# Main.net
KiCad netlist of a schematic drawn in EAGLE
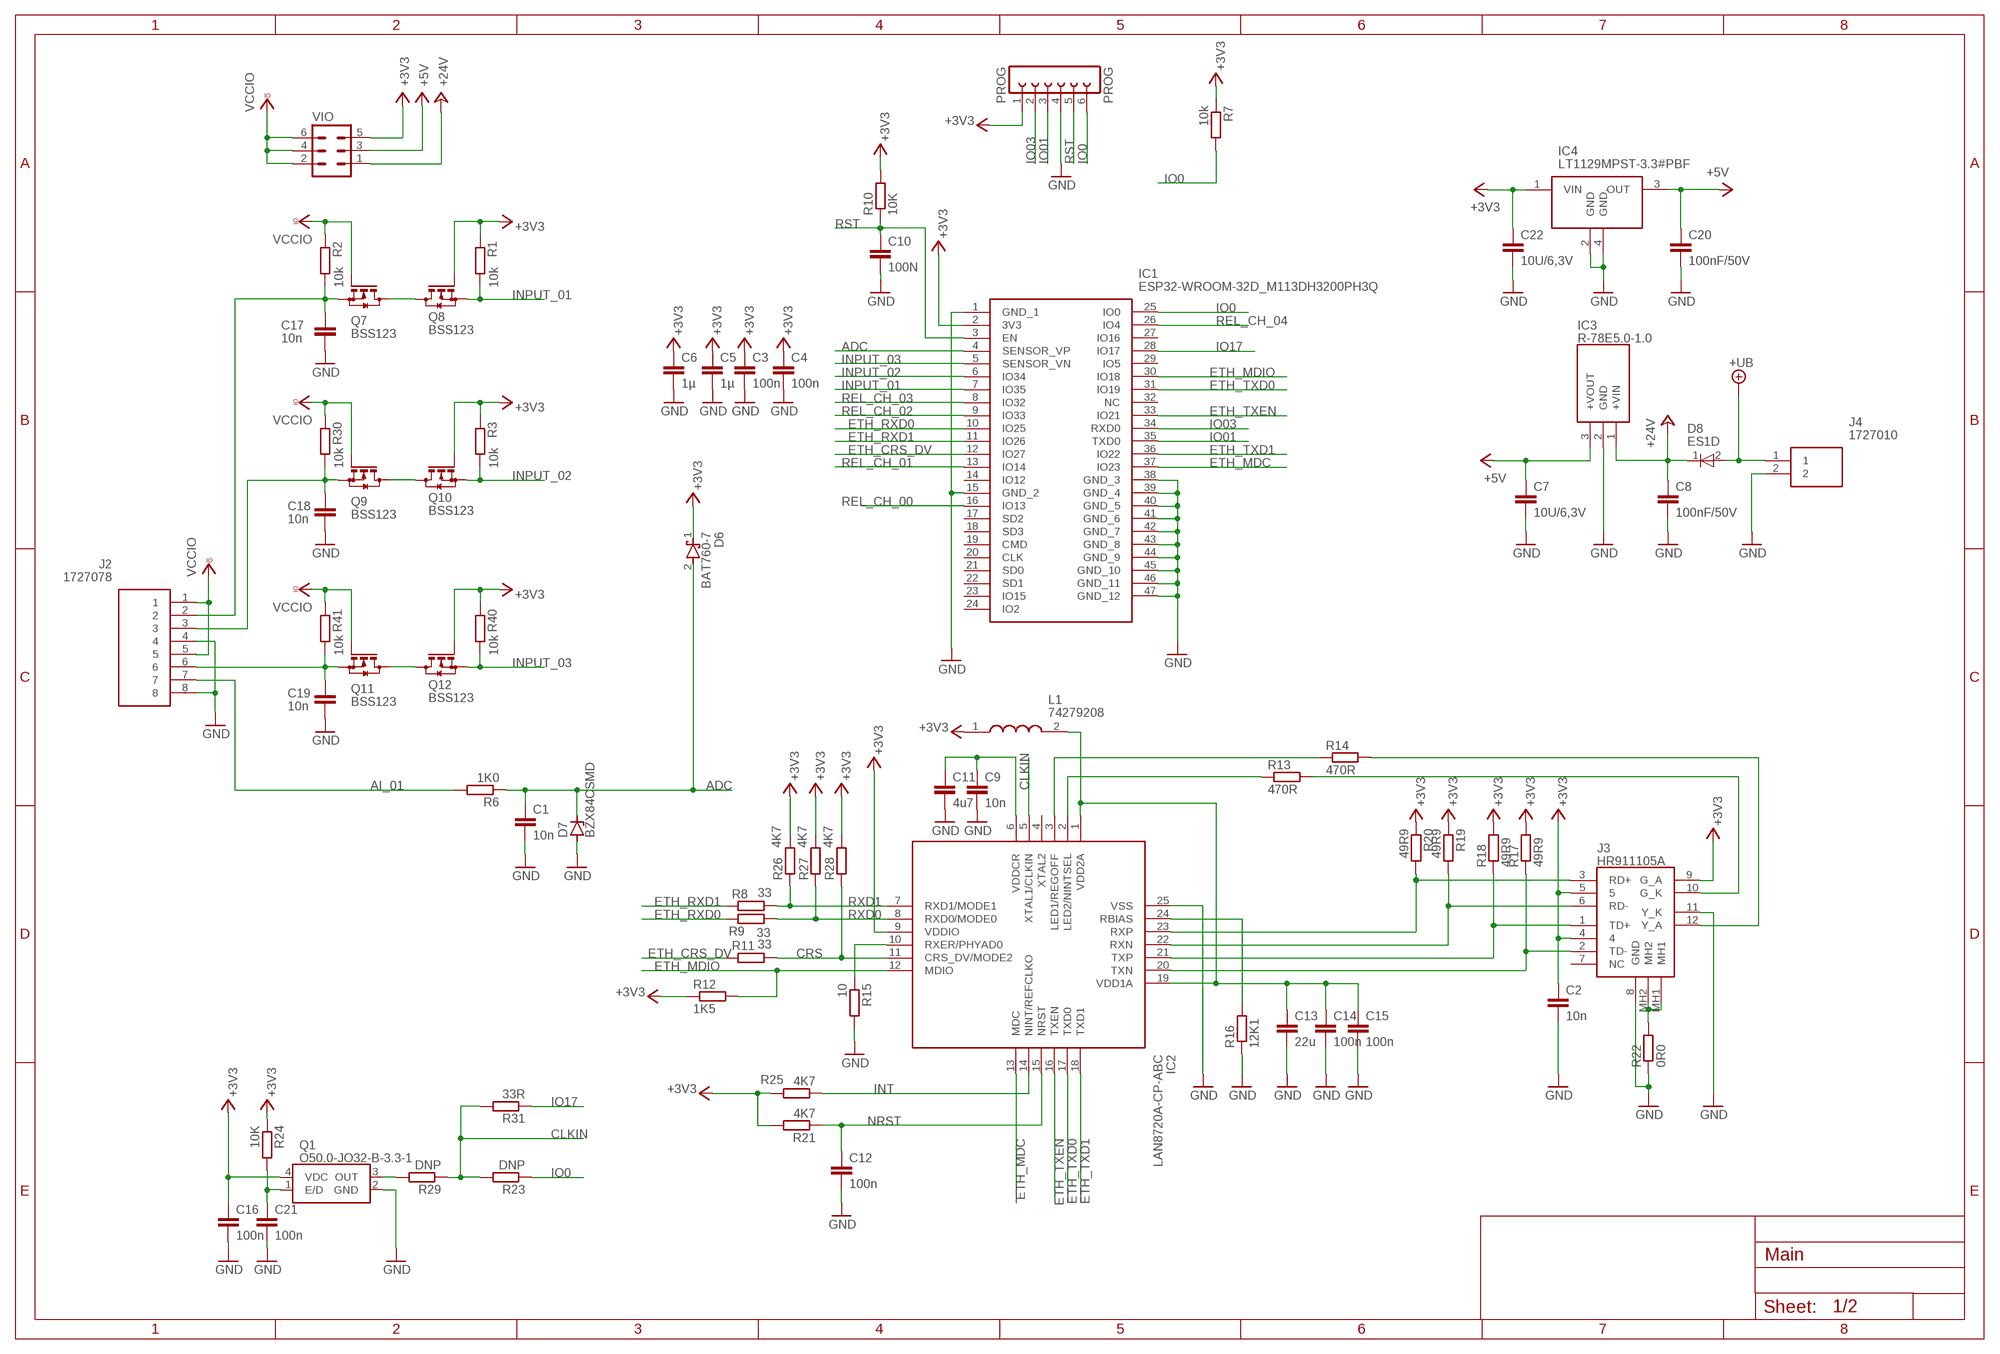
[diagram p0: schematic, sheet 1]
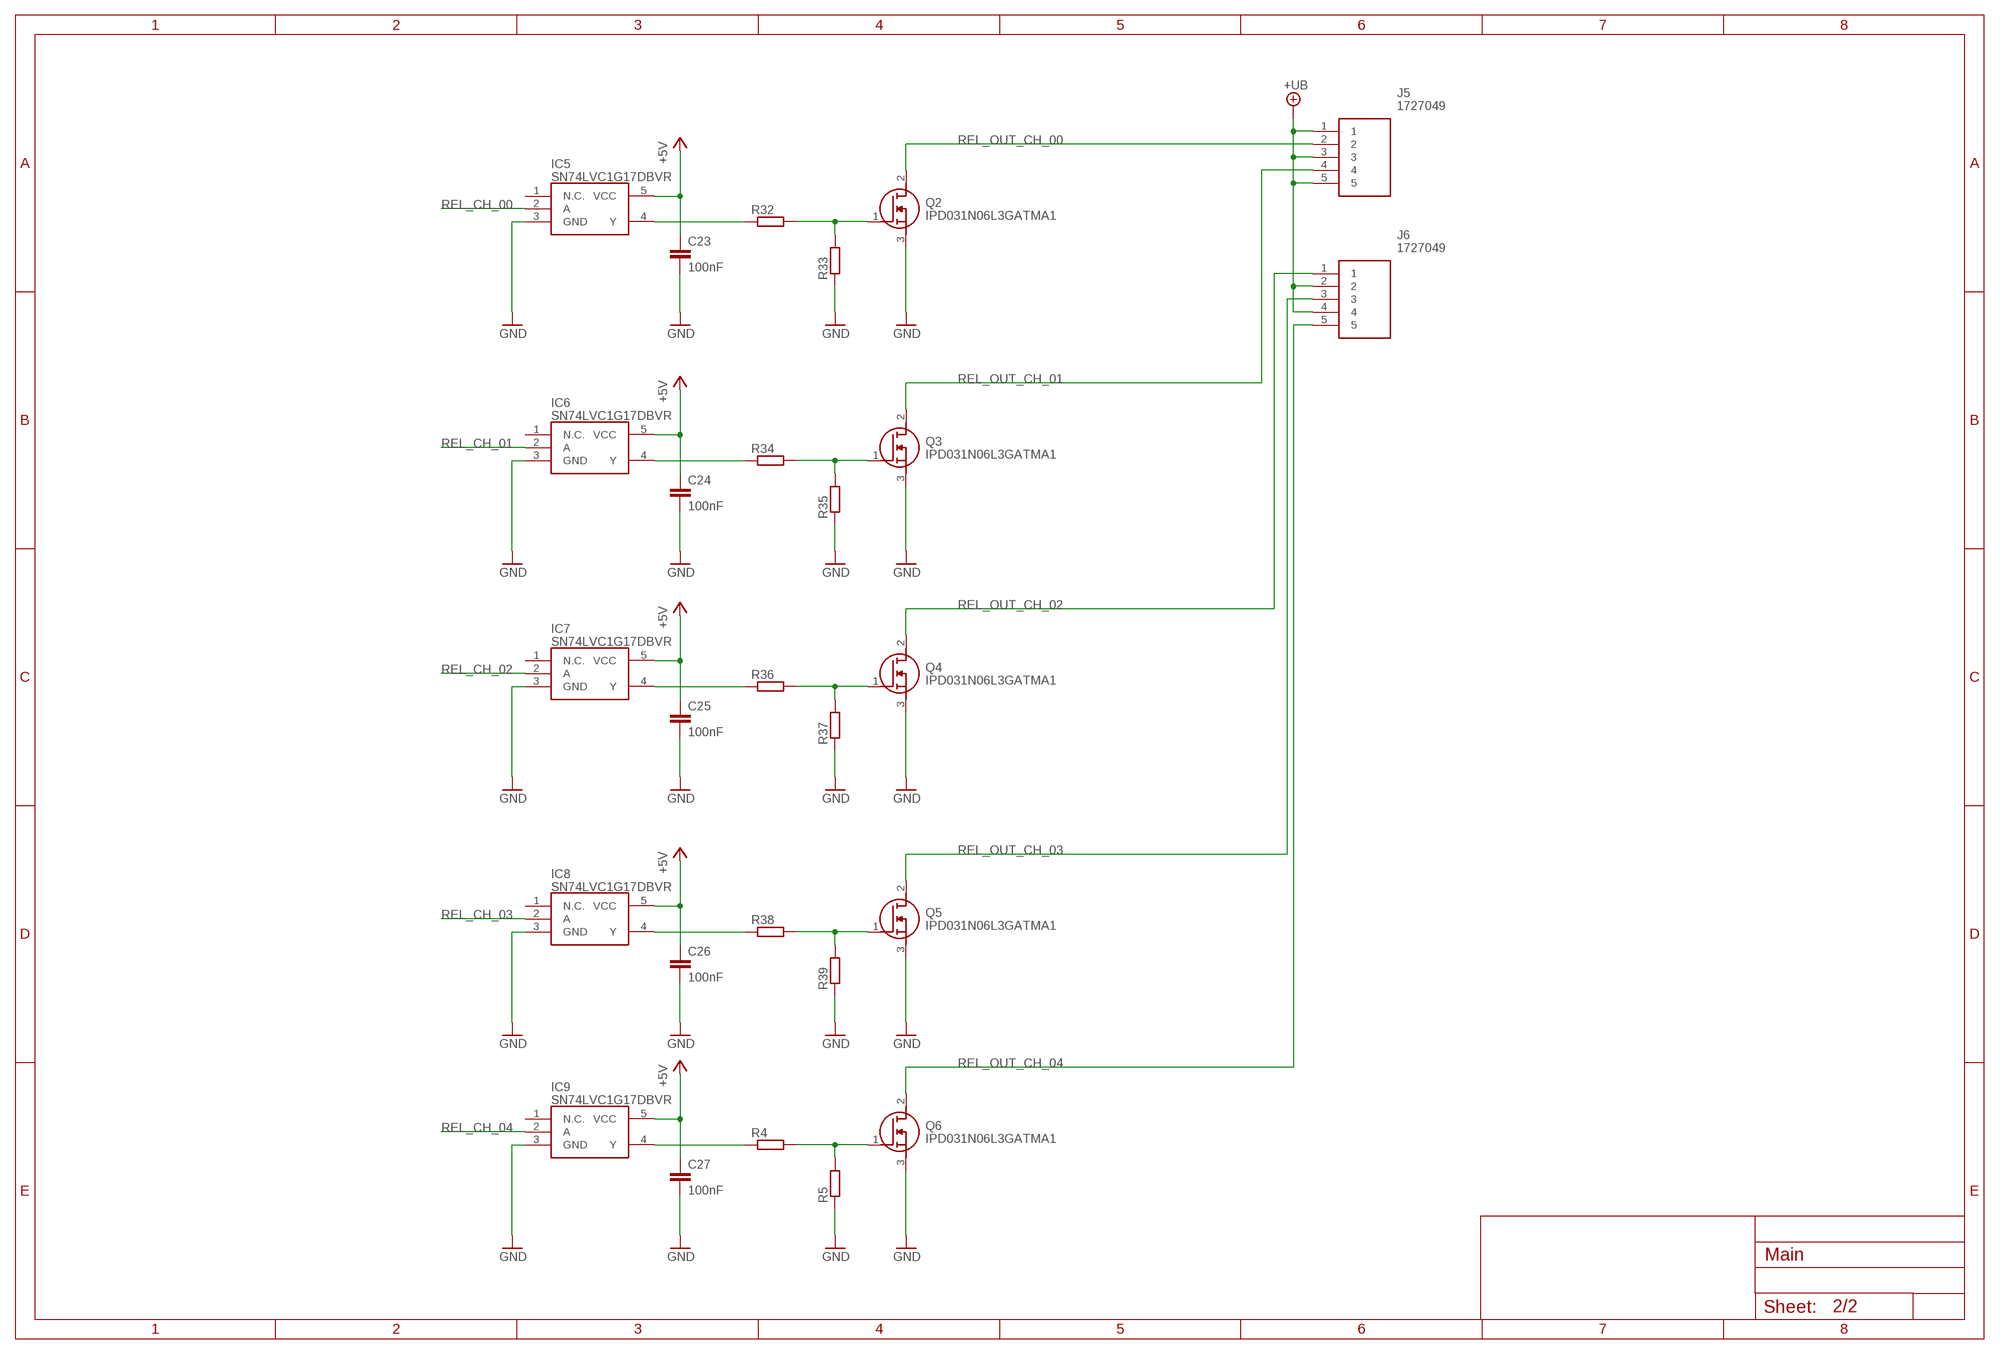
[diagram p1: schematic, sheet 2]

(export (version "E")
  (design (tool "Eeschema 10.0.6"))
  (components
    (comp (ref "C23")
      (value "100nF")
      (footprint "eagle-import:C0603")
      (libsource (lib "eagle-import") (part "C-EUC0603"))
    )
    (comp (ref "C24")
      (value "100nF")
      (footprint "eagle-import:C0603")
      (libsource (lib "eagle-import") (part "C-EUC0603"))
    )
    (comp (ref "C25")
      (value "100nF")
      (footprint "eagle-import:C0603")
      (libsource (lib "eagle-import") (part "C-EUC0603"))
    )
    (comp (ref "C26")
      (value "100nF")
      (footprint "eagle-import:C0603")
      (libsource (lib "eagle-import") (part "C-EUC0603"))
    )
    (comp (ref "C27")
      (value "100nF")
      (footprint "eagle-import:C0603")
      (libsource (lib "eagle-import") (part "C-EUC0603"))
    )
    (comp (ref "IC5")
      (value "SN74LVC1G17DBVR")
      (footprint "eagle-import:SOT95P280X145-5N")
      (fields (field (name "MOUSER_PART_NUMBER") "595-SN74LVC1G17DBVR"))
      (libsource (lib "eagle-import") (part "SN74LVC1G17DBVR"))
    )
    (comp (ref "IC6")
      (value "SN74LVC1G17DBVR")
      (footprint "eagle-import:SOT95P280X145-5N")
      (fields (field (name "MOUSER_PART_NUMBER") "595-SN74LVC1G17DBVR"))
      (libsource (lib "eagle-import") (part "SN74LVC1G17DBVR"))
    )
    (comp (ref "IC7")
      (value "SN74LVC1G17DBVR")
      (footprint "eagle-import:SOT95P280X145-5N")
      (fields (field (name "MOUSER_PART_NUMBER") "595-SN74LVC1G17DBVR"))
      (libsource (lib "eagle-import") (part "SN74LVC1G17DBVR"))
    )
    (comp (ref "IC8")
      (value "SN74LVC1G17DBVR")
      (footprint "eagle-import:SOT95P280X145-5N")
      (fields (field (name "MOUSER_PART_NUMBER") "595-SN74LVC1G17DBVR"))
      (libsource (lib "eagle-import") (part "SN74LVC1G17DBVR"))
    )
    (comp (ref "IC9")
      (value "SN74LVC1G17DBVR")
      (footprint "eagle-import:SOT95P280X145-5N")
      (fields (field (name "MOUSER_PART_NUMBER") "595-SN74LVC1G17DBVR"))
      (libsource (lib "eagle-import") (part "SN74LVC1G17DBVR"))
    )
    (comp (ref "J5")
      (value "1727049")
      (footprint "eagle-import:1727049")
      (fields (field (name "MOUSER_PART_NUMBER") "651-1727049"))
      (libsource (lib "eagle-import") (part "1727049"))
    )
    (comp (ref "J6")
      (value "1727049")
      (footprint "eagle-import:1727049")
      (fields (field (name "MOUSER_PART_NUMBER") "651-1727049"))
      (libsource (lib "eagle-import") (part "1727049"))
    )
    (comp (ref "Q2")
      (value "IPD031N06L3GATMA1")
      (footprint "eagle-import:IPD031N06L3GATMA1")
      (fields (field (name "MOUSER_PART_NUMBER") "726-IPD031N06L3GATMA"))
      (libsource (lib "eagle-import") (part "IPD031N06L3GATMA1"))
    )
    (comp (ref "Q3")
      (value "IPD031N06L3GATMA1")
      (footprint "eagle-import:IPD031N06L3GATMA1")
      (fields (field (name "MOUSER_PART_NUMBER") "726-IPD031N06L3GATMA"))
      (libsource (lib "eagle-import") (part "IPD031N06L3GATMA1"))
    )
    (comp (ref "Q4")
      (value "IPD031N06L3GATMA1")
      (footprint "eagle-import:IPD031N06L3GATMA1")
      (fields (field (name "MOUSER_PART_NUMBER") "726-IPD031N06L3GATMA"))
      (libsource (lib "eagle-import") (part "IPD031N06L3GATMA1"))
    )
    (comp (ref "Q5")
      (value "IPD031N06L3GATMA1")
      (footprint "eagle-import:IPD031N06L3GATMA1")
      (fields (field (name "MOUSER_PART_NUMBER") "726-IPD031N06L3GATMA"))
      (libsource (lib "eagle-import") (part "IPD031N06L3GATMA1"))
    )
    (comp (ref "Q6")
      (value "IPD031N06L3GATMA1")
      (footprint "eagle-import:IPD031N06L3GATMA1")
      (fields (field (name "MOUSER_PART_NUMBER") "726-IPD031N06L3GATMA"))
      (libsource (lib "eagle-import") (part "IPD031N06L3GATMA1"))
    )
    (comp (ref "R4")
      (value "R-EU_R0603")
      (footprint "eagle-import:R0603")
      (libsource (lib "eagle-import") (part "R-EU_R0603"))
    )
    (comp (ref "R5")
      (value "R-EU_R0603")
      (footprint "eagle-import:R0603")
      (libsource (lib "eagle-import") (part "R-EU_R0603"))
    )
    (comp (ref "R32")
      (value "R-EU_R0603")
      (footprint "eagle-import:R0603")
      (libsource (lib "eagle-import") (part "R-EU_R0603"))
    )
    (comp (ref "R33")
      (value "R-EU_R0603")
      (footprint "eagle-import:R0603")
      (libsource (lib "eagle-import") (part "R-EU_R0603"))
    )
    (comp (ref "R34")
      (value "R-EU_R0603")
      (footprint "eagle-import:R0603")
      (libsource (lib "eagle-import") (part "R-EU_R0603"))
    )
    (comp (ref "R35")
      (value "R-EU_R0603")
      (footprint "eagle-import:R0603")
      (libsource (lib "eagle-import") (part "R-EU_R0603"))
    )
    (comp (ref "R36")
      (value "R-EU_R0603")
      (footprint "eagle-import:R0603")
      (libsource (lib "eagle-import") (part "R-EU_R0603"))
    )
    (comp (ref "R37")
      (value "R-EU_R0603")
      (footprint "eagle-import:R0603")
      (libsource (lib "eagle-import") (part "R-EU_R0603"))
    )
    (comp (ref "R38")
      (value "R-EU_R0603")
      (footprint "eagle-import:R0603")
      (libsource (lib "eagle-import") (part "R-EU_R0603"))
    )
    (comp (ref "R39")
      (value "R-EU_R0603")
      (footprint "eagle-import:R0603")
      (libsource (lib "eagle-import") (part "R-EU_R0603"))
    )
    (comp (ref "C1")
      (value "10n")
      (footprint "eagle-import:C0603")
      (libsource (lib "eagle-import") (part "C-EUC0603"))
    )
    (comp (ref "C2")
      (value "10n")
      (footprint "eagle-import:C0603")
      (libsource (lib "eagle-import") (part "C-EUC0603"))
    )
    (comp (ref "C3")
      (value "100n")
      (footprint "eagle-import:C0603")
      (libsource (lib "eagle-import") (part "C-EUC0603"))
    )
    (comp (ref "C4")
      (value "100n")
      (footprint "eagle-import:C0603")
      (libsource (lib "eagle-import") (part "C-EUC0603"))
    )
    (comp (ref "C5")
      (value "1µ")
      (footprint "eagle-import:C0603")
      (libsource (lib "eagle-import") (part "C-EUC0603"))
    )
    (comp (ref "C6")
      (value "1µ")
      (footprint "eagle-import:C0603")
      (libsource (lib "eagle-import") (part "C-EUC0603"))
    )
    (comp (ref "C7")
      (value "10U/6,3V")
      (footprint "eagle-import:C0603")
      (libsource (lib "eagle-import") (part "C-EUC0603"))
    )
    (comp (ref "C8")
      (value "100nF/50V")
      (footprint "eagle-import:C0603")
      (libsource (lib "eagle-import") (part "C-EUC0603"))
    )
    (comp (ref "C9")
      (value "10n")
      (footprint "eagle-import:C0603")
      (libsource (lib "eagle-import") (part "C-EUC0603"))
    )
    (comp (ref "C10")
      (value "100N")
      (footprint "eagle-import:C0603")
      (libsource (lib "eagle-import") (part "C-EUC0603"))
    )
    (comp (ref "C11")
      (value "4u7")
      (footprint "eagle-import:C0603")
      (libsource (lib "eagle-import") (part "C-EUC0603"))
    )
    (comp (ref "C12")
      (value "100n")
      (footprint "eagle-import:C0603")
      (libsource (lib "eagle-import") (part "C-EUC0603"))
    )
    (comp (ref "C13")
      (value "22u")
      (footprint "eagle-import:C0603")
      (libsource (lib "eagle-import") (part "C-EUC0603"))
    )
    (comp (ref "C14")
      (value "100n")
      (footprint "eagle-import:C0603")
      (libsource (lib "eagle-import") (part "C-EUC0603"))
    )
    (comp (ref "C15")
      (value "100n")
      (footprint "eagle-import:C0603")
      (libsource (lib "eagle-import") (part "C-EUC0603"))
    )
    (comp (ref "C16")
      (value "100n")
      (footprint "eagle-import:C0603")
      (libsource (lib "eagle-import") (part "C-EUC0603"))
    )
    (comp (ref "C17")
      (value "10n")
      (footprint "eagle-import:C0603")
      (libsource (lib "eagle-import") (part "C-EUC0603"))
    )
    (comp (ref "C18")
      (value "10n")
      (footprint "eagle-import:C0603")
      (libsource (lib "eagle-import") (part "C-EUC0603"))
    )
    (comp (ref "C19")
      (value "10n")
      (footprint "eagle-import:C0603")
      (libsource (lib "eagle-import") (part "C-EUC0603"))
    )
    (comp (ref "C20")
      (value "100nF/50V")
      (footprint "eagle-import:C0603")
      (libsource (lib "eagle-import") (part "C-EUC0603"))
    )
    (comp (ref "C21")
      (value "100n")
      (footprint "eagle-import:C0603")
      (libsource (lib "eagle-import") (part "C-EUC0603"))
    )
    (comp (ref "C22")
      (value "10U/6,3V")
      (footprint "eagle-import:C0603")
      (libsource (lib "eagle-import") (part "C-EUC0603"))
    )
    (comp (ref "D6")
      (value "BAT760-7")
      (footprint "eagle-import:SOD2513X120N")
      (fields (field (name "MOUSER_PART_NUMBER") "621-BAT760-7"))
      (libsource (lib "eagle-import") (part "BAT760-7"))
    )
    (comp (ref "D7")
      (value "BZX84CSMD")
      (footprint "eagle-import:TO236")
      (libsource (lib "eagle-import") (part "BZX84CSMD"))
    )
    (comp (ref "D8")
      (value "ES1D")
      (footprint "eagle-import:SODFL3618X143N")
      (fields
        (field (name "ARROW_PART_NUMBER") "ES1DL R3G")
        (field (name "MOUSER_PART_NUMBER") "821-ES1DLR3G")
      )
      (libsource (lib "eagle-import") (part "ES1DL_R3G"))
    )
    (comp (ref "IC1")
      (value "ESP32-WROOM-32D_M113DH3200PH3Q")
      (footprint "eagle-import:ESP32WROOM32DM113DH3200PH3Q0")
      (fields
        (field (name "MANUFACTURER_PART_NUMBER") "ESP32-WROOM-32D(M113DH3200PH3Q0)")
        (field (name "MOUSER_PART_NUMBER") "356-ESP32WROOM-32D")
      )
      (libsource (lib "eagle-import") (part "ESP32-WROOM-32D_M113DH3200PH3Q"))
    )
    (comp (ref "IC2")
      (value "LAN8720A-CP-ABC")
      (footprint "eagle-import:QFN50P400X400X100-25N")
      (fields (field (name "MOUSER_PART_NUMBER") "579-LAN8720ACPABC"))
      (libsource (lib "eagle-import") (part "LAN8720A-CP-ABC"))
    )
    (comp (ref "IC3")
      (value "R-78E5.0-1.0")
      (footprint "eagle-import:R78E3310")
      (fields
        (field (name "ARROW_PART_NUMBER") "R-78E3.3-1.0")
        (field (name "MOUSER_PART_NUMBER") "919-R-78E3.3-1.0")
      )
      (libsource (lib "eagle-import") (part "R-78E3.3-1.0"))
    )
    (comp (ref "IC4")
      (value "LT1129MPST-3.3#PBF")
      (footprint "eagle-import:SOT230P700X180-4N")
      (fields (field (name "MOUSER_PART_NUMBER") "584-1129MPST-3.3PBF"))
      (libsource (lib "eagle-import") (part "LT1129MPST-3.3#PBF"))
    )
    (comp (ref "J2")
      (value "1727078")
      (footprint "eagle-import:1727078")
      (fields (field (name "MOUSER_PART_NUMBER") "651-1727078"))
      (libsource (lib "eagle-import") (part "1727078"))
    )
    (comp (ref "J3")
      (value "HR911105A")
      (footprint "eagle-import:HR911105A")
      (libsource (lib "eagle-import") (part "HR911105A"))
    )
    (comp (ref "J4")
      (value "1727010")
      (footprint "eagle-import:1727010")
      (fields (field (name "MOUSER_PART_NUMBER") "651-1727010"))
      (libsource (lib "eagle-import") (part "1727010"))
    )
    (comp (ref "L1")
      (value "74279208")
      (footprint "eagle-import:CAPC2012X90N")
      (fields (field (name "MOUSER_PART_NUMBER") "710-74279208"))
      (libsource (lib "eagle-import") (part "74279208"))
    )
    (comp (ref "PROG")
      (value "PROG")
      (footprint "eagle-import:FE06")
      (libsource (lib "eagle-import") (part "FE06-1"))
    )
    (comp (ref "Q1")
      (value "O50.0-JO32-B-3.3-1")
      (footprint "eagle-import:O200JO32B1V31T1LF")
      (libsource (lib "eagle-import") (part "O50.0-JO32-B-3.3-1"))
    )
    (comp (ref "Q7")
      (value "BSS123")
      (footprint "eagle-import:SOT23")
      (libsource (lib "eagle-import") (part "BSS123"))
    )
    (comp (ref "Q8")
      (value "BSS123")
      (footprint "eagle-import:SOT23")
      (libsource (lib "eagle-import") (part "BSS123"))
    )
    (comp (ref "Q9")
      (value "BSS123")
      (footprint "eagle-import:SOT23")
      (libsource (lib "eagle-import") (part "BSS123"))
    )
    (comp (ref "Q10")
      (value "BSS123")
      (footprint "eagle-import:SOT23")
      (libsource (lib "eagle-import") (part "BSS123"))
    )
    (comp (ref "Q11")
      (value "BSS123")
      (footprint "eagle-import:SOT23")
      (libsource (lib "eagle-import") (part "BSS123"))
    )
    (comp (ref "Q12")
      (value "BSS123")
      (footprint "eagle-import:SOT23")
      (libsource (lib "eagle-import") (part "BSS123"))
    )
    (comp (ref "R1")
      (value "10k")
      (footprint "eagle-import:R0603")
      (libsource (lib "eagle-import") (part "R-EU_R0603"))
    )
    (comp (ref "R2")
      (value "10k")
      (footprint "eagle-import:R0603")
      (libsource (lib "eagle-import") (part "R-EU_R0603"))
    )
    (comp (ref "R3")
      (value "10k")
      (footprint "eagle-import:R0603")
      (libsource (lib "eagle-import") (part "R-EU_R0603"))
    )
    (comp (ref "R6")
      (value "1K0")
      (footprint "eagle-import:R0603")
      (libsource (lib "eagle-import") (part "R-EU_R0603"))
    )
    (comp (ref "R7")
      (value "10k")
      (footprint "eagle-import:R0603")
      (libsource (lib "eagle-import") (part "R-EU_R0603"))
    )
    (comp (ref "R8")
      (value "33")
      (footprint "eagle-import:R0603")
      (libsource (lib "eagle-import") (part "R-EU_R0603"))
    )
    (comp (ref "R9")
      (value "33")
      (footprint "eagle-import:R0603")
      (libsource (lib "eagle-import") (part "R-EU_R0603"))
    )
    (comp (ref "R10")
      (value "10K")
      (footprint "eagle-import:R0603")
      (libsource (lib "eagle-import") (part "R-EU_R0603"))
    )
    (comp (ref "R11")
      (value "33")
      (footprint "eagle-import:R0603")
      (libsource (lib "eagle-import") (part "R-EU_R0603"))
    )
    (comp (ref "R12")
      (value "1K5")
      (footprint "eagle-import:R0603")
      (libsource (lib "eagle-import") (part "R-EU_R0603"))
    )
    (comp (ref "R13")
      (value "470R")
      (footprint "eagle-import:R0603")
      (libsource (lib "eagle-import") (part "R-EU_R0603"))
    )
    (comp (ref "R14")
      (value "470R")
      (footprint "eagle-import:R0603")
      (libsource (lib "eagle-import") (part "R-EU_R0603"))
    )
    (comp (ref "R15")
      (value "10")
      (footprint "eagle-import:R0603")
      (libsource (lib "eagle-import") (part "R-EU_R0603"))
    )
    (comp (ref "R16")
      (value "12K1")
      (footprint "eagle-import:R0603")
      (libsource (lib "eagle-import") (part "R-EU_R0603"))
    )
    (comp (ref "R17")
      (value "49R9")
      (footprint "eagle-import:R0603")
      (libsource (lib "eagle-import") (part "R-EU_R0603"))
    )
    (comp (ref "R18")
      (value "49R9")
      (footprint "eagle-import:R0603")
      (libsource (lib "eagle-import") (part "R-EU_R0603"))
    )
    (comp (ref "R19")
      (value "49R9")
      (footprint "eagle-import:R0603")
      (libsource (lib "eagle-import") (part "R-EU_R0603"))
    )
    (comp (ref "R20")
      (value "49R9")
      (footprint "eagle-import:R0603")
      (libsource (lib "eagle-import") (part "R-EU_R0603"))
    )
    (comp (ref "R21")
      (value "4K7")
      (footprint "eagle-import:R0603")
      (libsource (lib "eagle-import") (part "R-EU_R0603"))
    )
    (comp (ref "R22")
      (value "0R0")
      (footprint "eagle-import:R0603")
      (libsource (lib "eagle-import") (part "R-EU_R0603"))
    )
    (comp (ref "R23")
      (value "DNP")
      (footprint "eagle-import:R0603")
      (libsource (lib "eagle-import") (part "R-EU_R0603"))
    )
    (comp (ref "R24")
      (value "10K")
      (footprint "eagle-import:R0603")
      (libsource (lib "eagle-import") (part "R-EU_R0603"))
    )
    (comp (ref "R25")
      (value "4K7")
      (footprint "eagle-import:R0603")
      (libsource (lib "eagle-import") (part "R-EU_R0603"))
    )
    (comp (ref "R26")
      (value "4K7")
      (footprint "eagle-import:R0603")
      (libsource (lib "eagle-import") (part "R-EU_R0603"))
    )
    (comp (ref "R27")
      (value "4K7")
      (footprint "eagle-import:R0603")
      (libsource (lib "eagle-import") (part "R-EU_R0603"))
    )
    (comp (ref "R28")
      (value "4K7")
      (footprint "eagle-import:R0603")
      (libsource (lib "eagle-import") (part "R-EU_R0603"))
    )
    (comp (ref "R29")
      (value "DNP")
      (footprint "eagle-import:R0603")
      (libsource (lib "eagle-import") (part "R-EU_R0603"))
    )
    (comp (ref "R30")
      (value "10k")
      (footprint "eagle-import:R0603")
      (libsource (lib "eagle-import") (part "R-EU_R0603"))
    )
    (comp (ref "R31")
      (value "33R")
      (footprint "eagle-import:R0603")
      (libsource (lib "eagle-import") (part "R-EU_R0603"))
    )
    (comp (ref "R40")
      (value "10k")
      (footprint "eagle-import:R0603")
      (libsource (lib "eagle-import") (part "R-EU_R0603"))
    )
    (comp (ref "R41")
      (value "10k")
      (footprint "eagle-import:R0603")
      (libsource (lib "eagle-import") (part "R-EU_R0603"))
    )
    (comp (ref "VIO")
      (value "MA03-2")
      (footprint "eagle-import:MA03-2")
      (libsource (lib "eagle-import") (part "MA03-2"))
    )
  )
  (nets
    (net (code "1") (name "+3V3") (class "Default")
      (node (ref "C16") (pin "1") (pinfunction "1_1") (pintype "passive"))
      (node (ref "C2") (pin "1") (pinfunction "1_1") (pintype "passive"))
      (node (ref "C22") (pin "1") (pinfunction "1_1") (pintype "passive"))
      (node (ref "C3") (pin "1") (pinfunction "1_1") (pintype "passive"))
      (node (ref "C4") (pin "1") (pinfunction "1_1") (pintype "passive"))
      (node (ref "C5") (pin "1") (pinfunction "1_1") (pintype "passive"))
      (node (ref "C6") (pin "1") (pinfunction "1_1") (pintype "passive"))
      (node (ref "D6") (pin "1") (pinfunction "K_1") (pintype "passive"))
      (node (ref "IC1") (pin "2") (pinfunction "3V3_2") (pintype "bidirectional"))
      (node (ref "IC2") (pin "9") (pinfunction "VDDIO_9") (pintype "bidirectional"))
      (node (ref "IC4") (pin "1") (pinfunction "VIN_1") (pintype "bidirectional"))
      (node (ref "J3") (pin "4") (pinfunction "4_4") (pintype "bidirectional"))
      (node (ref "J3") (pin "5") (pinfunction "5_5") (pintype "bidirectional"))
      (node (ref "J3") (pin "9") (pinfunction "G_A_9") (pintype "bidirectional"))
      (node (ref "L1") (pin "1") (pinfunction "1_1") (pintype "bidirectional"))
      (node (ref "PROG") (pin "1") (pinfunction "1_1") (pintype "passive"))
      (node (ref "Q1") (pin "4") (pinfunction "VDC_4") (pintype "bidirectional"))
      (node (ref "Q10") (pin "1") (pinfunction "G_1") (pintype "passive"))
      (node (ref "Q12") (pin "1") (pinfunction "G_1") (pintype "passive"))
      (node (ref "Q8") (pin "1") (pinfunction "G_1") (pintype "passive"))
      (node (ref "R1") (pin "1") (pinfunction "1_1") (pintype "passive"))
      (node (ref "R10") (pin "2") (pinfunction "2_2") (pintype "passive"))
      (node (ref "R12") (pin "1") (pinfunction "1_1") (pintype "passive"))
      (node (ref "R17") (pin "2") (pinfunction "2_2") (pintype "passive"))
      (node (ref "R18") (pin "2") (pinfunction "2_2") (pintype "passive"))
      (node (ref "R19") (pin "1") (pinfunction "1_1") (pintype "passive"))
      (node (ref "R20") (pin "1") (pinfunction "1_1") (pintype "passive"))
      (node (ref "R21") (pin "2") (pinfunction "2_2") (pintype "passive"))
      (node (ref "R24") (pin "1") (pinfunction "1_1") (pintype "passive"))
      (node (ref "R25") (pin "2") (pinfunction "2_2") (pintype "passive"))
      (node (ref "R26") (pin "2") (pinfunction "2_2") (pintype "passive"))
      (node (ref "R27") (pin "2") (pinfunction "2_2") (pintype "passive"))
      (node (ref "R28") (pin "2") (pinfunction "2_2") (pintype "passive"))
      (node (ref "R3") (pin "1") (pinfunction "1_1") (pintype "passive"))
      (node (ref "R40") (pin "1") (pinfunction "1_1") (pintype "passive"))
      (node (ref "R7") (pin "1") (pinfunction "1_1") (pintype "passive"))
      (node (ref "VIO") (pin "5") (pinfunction "5_5") (pintype "passive"))
    )
    (net (code "2") (name "+5V") (class "Default")
      (node (ref "C20") (pin "1") (pinfunction "1_1") (pintype "passive"))
      (node (ref "C23") (pin "1") (pinfunction "1_1") (pintype "passive"))
      (node (ref "C24") (pin "1") (pinfunction "1_1") (pintype "passive"))
      (node (ref "C25") (pin "1") (pinfunction "1_1") (pintype "passive"))
      (node (ref "C26") (pin "1") (pinfunction "1_1") (pintype "passive"))
      (node (ref "C27") (pin "1") (pinfunction "1_1") (pintype "passive"))
      (node (ref "C7") (pin "1") (pinfunction "1_1") (pintype "passive"))
      (node (ref "IC3") (pin "3") (pinfunction "+VOUT_3") (pintype "bidirectional"))
      (node (ref "IC4") (pin "3") (pinfunction "OUT_3") (pintype "bidirectional"))
      (node (ref "IC5") (pin "5") (pinfunction "VCC_5") (pintype "bidirectional"))
      (node (ref "IC6") (pin "5") (pinfunction "VCC_5") (pintype "bidirectional"))
      (node (ref "IC7") (pin "5") (pinfunction "VCC_5") (pintype "bidirectional"))
      (node (ref "IC8") (pin "5") (pinfunction "VCC_5") (pintype "bidirectional"))
      (node (ref "IC9") (pin "5") (pinfunction "VCC_5") (pintype "bidirectional"))
      (node (ref "VIO") (pin "3") (pinfunction "3_3") (pintype "passive"))
    )
    (net (code "3") (name "+24V") (class "Default")
      (node (ref "C8") (pin "1") (pinfunction "1_1") (pintype "passive"))
      (node (ref "D8") (pin "1") (pinfunction "K_1") (pintype "bidirectional"))
      (node (ref "IC3") (pin "1") (pinfunction "+VIN_1") (pintype "bidirectional"))
      (node (ref "VIO") (pin "1") (pinfunction "1_1") (pintype "passive"))
    )
    (net (code "4") (name "+UB") (class "Default")
      (node (ref "D8") (pin "2") (pinfunction "A_2") (pintype "bidirectional"))
      (node (ref "J4") (pin "1") (pinfunction "1_1") (pintype "bidirectional"))
      (node (ref "J5") (pin "1") (pinfunction "1_1") (pintype "bidirectional"))
      (node (ref "J5") (pin "3") (pinfunction "3_3") (pintype "bidirectional"))
      (node (ref "J5") (pin "5") (pinfunction "5_5") (pintype "bidirectional"))
      (node (ref "J6") (pin "2") (pinfunction "2_2") (pintype "bidirectional"))
      (node (ref "J6") (pin "4") (pinfunction "4_4") (pintype "bidirectional"))
    )
    (net (code "5") (name "ADC") (class "Default")
      (node (ref "C1") (pin "1") (pinfunction "1_1") (pintype "passive"))
      (node (ref "D6") (pin "2") (pinfunction "A_2") (pintype "passive"))
      (node (ref "D7") (pin "C") (pinfunction "C_C") (pintype "passive"))
      (node (ref "IC1") (pin "4") (pinfunction "SENSOR_VP_4") (pintype "bidirectional"))
      (node (ref "R6") (pin "1") (pinfunction "1_1") (pintype "passive"))
    )
    (net (code "6") (name "AI_01") (class "Default")
      (node (ref "J2") (pin "7") (pinfunction "7_7") (pintype "bidirectional"))
      (node (ref "R6") (pin "2") (pinfunction "2_2") (pintype "passive"))
    )
    (net (code "7") (name "CLKIN") (class "Default")
      (node (ref "IC2") (pin "5") (pinfunction "XTAL1/CLKIN_5") (pintype "bidirectional"))
      (node (ref "R23") (pin "2") (pinfunction "2_2") (pintype "passive"))
      (node (ref "R29") (pin "1") (pinfunction "1_1") (pintype "passive"))
      (node (ref "R31") (pin "2") (pinfunction "2_2") (pintype "passive"))
    )
    (net (code "8") (name "CRS") (class "Default")
      (node (ref "IC2") (pin "11") (pinfunction "CRS_DV/MODE2_11") (pintype "bidirectional"))
      (node (ref "R11") (pin "2") (pinfunction "2_2") (pintype "passive"))
      (node (ref "R28") (pin "1") (pinfunction "1_1") (pintype "passive"))
    )
    (net (code "9") (name "ETH_CRS_DV") (class "Default")
      (node (ref "IC1") (pin "12") (pinfunction "IO27_12") (pintype "bidirectional"))
      (node (ref "R11") (pin "1") (pinfunction "1_1") (pintype "passive"))
    )
    (net (code "10") (name "ETH_MDC") (class "Default")
      (node (ref "IC1") (pin "37") (pinfunction "IO23_37") (pintype "bidirectional"))
      (node (ref "IC2") (pin "13") (pinfunction "MDC_13") (pintype "bidirectional"))
    )
    (net (code "11") (name "ETH_MDIO") (class "Default")
      (node (ref "IC1") (pin "30") (pinfunction "IO18_30") (pintype "bidirectional"))
      (node (ref "IC2") (pin "12") (pinfunction "MDIO_12") (pintype "bidirectional"))
      (node (ref "R12") (pin "2") (pinfunction "2_2") (pintype "passive"))
    )
    (net (code "12") (name "ETH_RXD0") (class "Default")
      (node (ref "IC1") (pin "10") (pinfunction "IO25_10") (pintype "bidirectional"))
      (node (ref "R9") (pin "1") (pinfunction "1_1") (pintype "passive"))
    )
    (net (code "13") (name "ETH_RXD1") (class "Default")
      (node (ref "IC1") (pin "11") (pinfunction "IO26_11") (pintype "bidirectional"))
      (node (ref "R8") (pin "1") (pinfunction "1_1") (pintype "passive"))
    )
    (net (code "14") (name "ETH_TXD0") (class "Default")
      (node (ref "IC1") (pin "31") (pinfunction "IO19_31") (pintype "bidirectional"))
      (node (ref "IC2") (pin "17") (pinfunction "TXD0_17") (pintype "bidirectional"))
    )
    (net (code "15") (name "ETH_TXD1") (class "Default")
      (node (ref "IC1") (pin "36") (pinfunction "IO22_36") (pintype "bidirectional"))
      (node (ref "IC2") (pin "18") (pinfunction "TXD1_18") (pintype "bidirectional"))
    )
    (net (code "16") (name "ETH_TXEN") (class "Default")
      (node (ref "IC1") (pin "33") (pinfunction "IO21_33") (pintype "bidirectional"))
      (node (ref "IC2") (pin "16") (pinfunction "TXEN_16") (pintype "bidirectional"))
    )
    (net (code "17") (name "GND") (class "Default")
      (node (ref "C1") (pin "2") (pinfunction "2_2") (pintype "passive"))
      (node (ref "C10") (pin "2") (pinfunction "2_2") (pintype "passive"))
      (node (ref "C11") (pin "2") (pinfunction "2_2") (pintype "passive"))
      (node (ref "C12") (pin "2") (pinfunction "2_2") (pintype "passive"))
      (node (ref "C13") (pin "2") (pinfunction "2_2") (pintype "passive"))
      (node (ref "C14") (pin "2") (pinfunction "2_2") (pintype "passive"))
      (node (ref "C15") (pin "2") (pinfunction "2_2") (pintype "passive"))
      (node (ref "C16") (pin "2") (pinfunction "2_2") (pintype "passive"))
      (node (ref "C17") (pin "2") (pinfunction "2_2") (pintype "passive"))
      (node (ref "C18") (pin "2") (pinfunction "2_2") (pintype "passive"))
      (node (ref "C19") (pin "2") (pinfunction "2_2") (pintype "passive"))
      (node (ref "C2") (pin "2") (pinfunction "2_2") (pintype "passive"))
      (node (ref "C20") (pin "2") (pinfunction "2_2") (pintype "passive"))
      (node (ref "C21") (pin "2") (pinfunction "2_2") (pintype "passive"))
      (node (ref "C22") (pin "2") (pinfunction "2_2") (pintype "passive"))
      (node (ref "C23") (pin "2") (pinfunction "2_2") (pintype "passive"))
      (node (ref "C24") (pin "2") (pinfunction "2_2") (pintype "passive"))
      (node (ref "C25") (pin "2") (pinfunction "2_2") (pintype "passive"))
      (node (ref "C26") (pin "2") (pinfunction "2_2") (pintype "passive"))
      (node (ref "C27") (pin "2") (pinfunction "2_2") (pintype "passive"))
      (node (ref "C3") (pin "2") (pinfunction "2_2") (pintype "passive"))
      (node (ref "C4") (pin "2") (pinfunction "2_2") (pintype "passive"))
      (node (ref "C5") (pin "2") (pinfunction "2_2") (pintype "passive"))
      (node (ref "C6") (pin "2") (pinfunction "2_2") (pintype "passive"))
      (node (ref "C7") (pin "2") (pinfunction "2_2") (pintype "passive"))
      (node (ref "C8") (pin "2") (pinfunction "2_2") (pintype "passive"))
      (node (ref "C9") (pin "2") (pinfunction "2_2") (pintype "passive"))
      (node (ref "D7") (pin "A") (pinfunction "A_A") (pintype "passive"))
      (node (ref "IC1") (pin "1") (pinfunction "GND_1_1") (pintype "bidirectional"))
      (node (ref "IC1") (pin "15") (pinfunction "GND_2_15") (pintype "bidirectional"))
      (node (ref "IC1") (pin "38") (pinfunction "GND_3_38") (pintype "bidirectional"))
      (node (ref "IC1") (pin "39") (pinfunction "GND_4_39") (pintype "bidirectional"))
      (node (ref "IC1") (pin "40") (pinfunction "GND_5_40") (pintype "bidirectional"))
      (node (ref "IC1") (pin "41") (pinfunction "GND_6_41") (pintype "bidirectional"))
      (node (ref "IC1") (pin "42") (pinfunction "GND_7_42") (pintype "bidirectional"))
      (node (ref "IC1") (pin "43") (pinfunction "GND_8_43") (pintype "bidirectional"))
      (node (ref "IC1") (pin "44") (pinfunction "GND_9_44") (pintype "bidirectional"))
      (node (ref "IC1") (pin "45") (pinfunction "GND_10_45") (pintype "bidirectional"))
      (node (ref "IC1") (pin "46") (pinfunction "GND_11_46") (pintype "bidirectional"))
      (node (ref "IC1") (pin "47") (pinfunction "GND_12_47") (pintype "bidirectional"))
      (node (ref "IC2") (pin "25") (pinfunction "VSS_25") (pintype "bidirectional"))
      (node (ref "IC3") (pin "2") (pinfunction "GND_2") (pintype "bidirectional"))
      (node (ref "IC4") (pin "2") (pinfunction "GND_2") (pintype "bidirectional"))
      (node (ref "IC4") (pin "4") (pinfunction "GND._4") (pintype "bidirectional"))
      (node (ref "IC5") (pin "3") (pinfunction "GND_3") (pintype "bidirectional"))
      (node (ref "IC6") (pin "3") (pinfunction "GND_3") (pintype "bidirectional"))
      (node (ref "IC7") (pin "3") (pinfunction "GND_3") (pintype "bidirectional"))
      (node (ref "IC8") (pin "3") (pinfunction "GND_3") (pintype "bidirectional"))
      (node (ref "IC9") (pin "3") (pinfunction "GND_3") (pintype "bidirectional"))
      (node (ref "J2") (pin "4") (pinfunction "4_4") (pintype "bidirectional"))
      (node (ref "J2") (pin "8") (pinfunction "8_8") (pintype "bidirectional"))
      (node (ref "J3") (pin "11") (pinfunction "Y_K_11") (pintype "bidirectional"))
      (node (ref "J3") (pin "8") (pinfunction "GND_8") (pintype "bidirectional"))
      (node (ref "J4") (pin "2") (pinfunction "2_2") (pintype "bidirectional"))
      (node (ref "PROG") (pin "4") (pinfunction "4_4") (pintype "passive"))
      (node (ref "Q1") (pin "2") (pinfunction "GND_2") (pintype "bidirectional"))
      (node (ref "Q2") (pin "3") (pinfunction "S_3") (pintype "bidirectional"))
      (node (ref "Q3") (pin "3") (pinfunction "S_3") (pintype "bidirectional"))
      (node (ref "Q4") (pin "3") (pinfunction "S_3") (pintype "bidirectional"))
      (node (ref "Q5") (pin "3") (pinfunction "S_3") (pintype "bidirectional"))
      (node (ref "Q6") (pin "3") (pinfunction "S_3") (pintype "bidirectional"))
      (node (ref "R15") (pin "2") (pinfunction "2_2") (pintype "passive"))
      (node (ref "R16") (pin "1") (pinfunction "1_1") (pintype "passive"))
      (node (ref "R22") (pin "1") (pinfunction "1_1") (pintype "passive"))
      (node (ref "R33") (pin "1") (pinfunction "1_1") (pintype "passive"))
      (node (ref "R35") (pin "1") (pinfunction "1_1") (pintype "passive"))
      (node (ref "R37") (pin "1") (pinfunction "1_1") (pintype "passive"))
      (node (ref "R39") (pin "1") (pinfunction "1_1") (pintype "passive"))
      (node (ref "R5") (pin "1") (pinfunction "1_1") (pintype "passive"))
    )
    (net (code "18") (name "INPUT_01") (class "Default")
      (node (ref "IC1") (pin "7") (pinfunction "IO35_7") (pintype "bidirectional"))
      (node (ref "Q8") (pin "2") (pinfunction "S_2") (pintype "passive"))
      (node (ref "R1") (pin "2") (pinfunction "2_2") (pintype "passive"))
    )
    (net (code "19") (name "INPUT_02") (class "Default")
      (node (ref "IC1") (pin "6") (pinfunction "IO34_6") (pintype "bidirectional"))
      (node (ref "Q10") (pin "2") (pinfunction "S_2") (pintype "passive"))
      (node (ref "R3") (pin "2") (pinfunction "2_2") (pintype "passive"))
    )
    (net (code "20") (name "INPUT_03") (class "Default")
      (node (ref "IC1") (pin "5") (pinfunction "SENSOR_VN_5") (pintype "bidirectional"))
      (node (ref "Q12") (pin "2") (pinfunction "S_2") (pintype "passive"))
      (node (ref "R40") (pin "2") (pinfunction "2_2") (pintype "passive"))
    )
    (net (code "21") (name "INT") (class "Default")
      (node (ref "IC2") (pin "14") (pinfunction "NINT/REFCLKO_14") (pintype "bidirectional"))
      (node (ref "R25") (pin "1") (pinfunction "1_1") (pintype "passive"))
    )
    (net (code "22") (name "IO0") (class "Default")
      (node (ref "IC1") (pin "25") (pinfunction "IO0_25") (pintype "bidirectional"))
      (node (ref "PROG") (pin "6") (pinfunction "6_6") (pintype "passive"))
      (node (ref "R23") (pin "1") (pinfunction "1_1") (pintype "passive"))
      (node (ref "R7") (pin "2") (pinfunction "2_2") (pintype "passive"))
    )
    (net (code "23") (name "IO01") (class "Default")
      (node (ref "IC1") (pin "35") (pinfunction "TXD0_35") (pintype "bidirectional"))
      (node (ref "PROG") (pin "3") (pinfunction "3_3") (pintype "passive"))
    )
    (net (code "24") (name "IO03") (class "Default")
      (node (ref "IC1") (pin "34") (pinfunction "RXD0_34") (pintype "bidirectional"))
      (node (ref "PROG") (pin "2") (pinfunction "2_2") (pintype "passive"))
    )
    (net (code "25") (name "IO17") (class "Default")
      (node (ref "IC1") (pin "28") (pinfunction "IO17_28") (pintype "bidirectional"))
      (node (ref "R31") (pin "1") (pinfunction "1_1") (pintype "passive"))
    )
    (net (code "26") (name "NRST") (class "Default")
      (node (ref "C12") (pin "1") (pinfunction "1_1") (pintype "passive"))
      (node (ref "IC2") (pin "15") (pinfunction "NRST_15") (pintype "bidirectional"))
      (node (ref "R21") (pin "1") (pinfunction "1_1") (pintype "passive"))
    )
    (net (code "27") (name "Net-(IC2-LED1{slash}REGOFF)") (class "Default")
      (node (ref "IC2") (pin "3") (pinfunction "LED1/REGOFF_3") (pintype "bidirectional"))
      (node (ref "R14") (pin "1") (pinfunction "1_1") (pintype "passive"))
    )
    (net (code "28") (name "Net-(IC2-LED2{slash}NINTSEL)") (class "Default")
      (node (ref "IC2") (pin "2") (pinfunction "LED2/NINTSEL_2") (pintype "bidirectional"))
      (node (ref "R13") (pin "1") (pinfunction "1_1") (pintype "passive"))
    )
    (net (code "29") (name "Net-(IC2-RBIAS)") (class "Default")
      (node (ref "IC2") (pin "24") (pinfunction "RBIAS_24") (pintype "bidirectional"))
      (node (ref "R16") (pin "2") (pinfunction "2_2") (pintype "passive"))
    )
    (net (code "30") (name "Net-(IC2-RXER{slash}PHYAD0)") (class "Default")
      (node (ref "IC2") (pin "10") (pinfunction "RXER/PHYAD0_10") (pintype "bidirectional"))
      (node (ref "R15") (pin "1") (pinfunction "1_1") (pintype "passive"))
    )
    (net (code "31") (name "Net-(IC2-RXN)") (class "Default")
      (node (ref "IC2") (pin "22") (pinfunction "RXN_22") (pintype "bidirectional"))
      (node (ref "J3") (pin "6") (pinfunction "RD-_6") (pintype "bidirectional"))
      (node (ref "R19") (pin "2") (pinfunction "2_2") (pintype "passive"))
    )
    (net (code "32") (name "Net-(IC2-RXP)") (class "Default")
      (node (ref "IC2") (pin "23") (pinfunction "RXP_23") (pintype "bidirectional"))
      (node (ref "J3") (pin "3") (pinfunction "RD+_3") (pintype "bidirectional"))
      (node (ref "R20") (pin "2") (pinfunction "2_2") (pintype "passive"))
    )
    (net (code "33") (name "Net-(IC2-TXN)") (class "Default")
      (node (ref "IC2") (pin "20") (pinfunction "TXN_20") (pintype "bidirectional"))
      (node (ref "J3") (pin "2") (pinfunction "TD-_2") (pintype "bidirectional"))
      (node (ref "R17") (pin "1") (pinfunction "1_1") (pintype "passive"))
    )
    (net (code "34") (name "Net-(IC2-TXP)") (class "Default")
      (node (ref "IC2") (pin "21") (pinfunction "TXP_21") (pintype "bidirectional"))
      (node (ref "J3") (pin "1") (pinfunction "TD+_1") (pintype "bidirectional"))
      (node (ref "R18") (pin "1") (pinfunction "1_1") (pintype "passive"))
    )
    (net (code "35") (name "Net-(IC2-VDD1A)") (class "Default")
      (node (ref "C13") (pin "1") (pinfunction "1_1") (pintype "passive"))
      (node (ref "C14") (pin "1") (pinfunction "1_1") (pintype "passive"))
      (node (ref "C15") (pin "1") (pinfunction "1_1") (pintype "passive"))
      (node (ref "IC2") (pin "1") (pinfunction "VDD2A_1") (pintype "bidirectional"))
      (node (ref "IC2") (pin "19") (pinfunction "VDD1A_19") (pintype "bidirectional"))
      (node (ref "L1") (pin "2") (pinfunction "2_2") (pintype "bidirectional"))
    )
    (net (code "36") (name "Net-(IC2-VDDCR)") (class "Default")
      (node (ref "C11") (pin "1") (pinfunction "1_1") (pintype "passive"))
      (node (ref "C9") (pin "1") (pinfunction "1_1") (pintype "passive"))
      (node (ref "IC2") (pin "6") (pinfunction "VDDCR_6") (pintype "bidirectional"))
    )
    (net (code "37") (name "Net-(IC5-Y)") (class "Default")
      (node (ref "IC5") (pin "4") (pinfunction "Y_4") (pintype "bidirectional"))
      (node (ref "R32") (pin "1") (pinfunction "1_1") (pintype "passive"))
    )
    (net (code "38") (name "Net-(IC6-Y)") (class "Default")
      (node (ref "IC6") (pin "4") (pinfunction "Y_4") (pintype "bidirectional"))
      (node (ref "R34") (pin "1") (pinfunction "1_1") (pintype "passive"))
    )
    (net (code "39") (name "Net-(IC7-Y)") (class "Default")
      (node (ref "IC7") (pin "4") (pinfunction "Y_4") (pintype "bidirectional"))
      (node (ref "R36") (pin "1") (pinfunction "1_1") (pintype "passive"))
    )
    (net (code "40") (name "Net-(IC8-Y)") (class "Default")
      (node (ref "IC8") (pin "4") (pinfunction "Y_4") (pintype "bidirectional"))
      (node (ref "R38") (pin "1") (pinfunction "1_1") (pintype "passive"))
    )
    (net (code "41") (name "Net-(IC9-Y)") (class "Default")
      (node (ref "IC9") (pin "4") (pinfunction "Y_4") (pintype "bidirectional"))
      (node (ref "R4") (pin "1") (pinfunction "1_1") (pintype "passive"))
    )
    (net (code "42") (name "Net-(J3-G_K)") (class "Default")
      (node (ref "J3") (pin "10") (pinfunction "G_K_10") (pintype "bidirectional"))
      (node (ref "R13") (pin "2") (pinfunction "2_2") (pintype "passive"))
    )
    (net (code "43") (name "Net-(J3-PadMH1)") (class "Default")
      (node (ref "J3") (pin "MH1") (pinfunction "MH1_MH1") (pintype "bidirectional"))
      (node (ref "J3") (pin "MH2") (pinfunction "MH2_MH2") (pintype "bidirectional"))
      (node (ref "R22") (pin "2") (pinfunction "2_2") (pintype "passive"))
    )
    (net (code "44") (name "Net-(J3-Y_A)") (class "Default")
      (node (ref "J3") (pin "12") (pinfunction "Y_A_12") (pintype "bidirectional"))
      (node (ref "R14") (pin "2") (pinfunction "2_2") (pintype "passive"))
    )
    (net (code "45") (name "Net-(Q1-E{slash}D)") (class "Default")
      (node (ref "C21") (pin "1") (pinfunction "1_1") (pintype "passive"))
      (node (ref "Q1") (pin "1") (pinfunction "E/D_1") (pintype "bidirectional"))
      (node (ref "R24") (pin "2") (pinfunction "2_2") (pintype "passive"))
    )
    (net (code "46") (name "Net-(Q1-OUT)") (class "Default")
      (node (ref "Q1") (pin "3") (pinfunction "OUT_3") (pintype "bidirectional"))
      (node (ref "R29") (pin "2") (pinfunction "2_2") (pintype "passive"))
    )
    (net (code "47") (name "Net-(Q2-G)") (class "Default")
      (node (ref "Q2") (pin "1") (pinfunction "G_1") (pintype "bidirectional"))
      (node (ref "R32") (pin "2") (pinfunction "2_2") (pintype "passive"))
      (node (ref "R33") (pin "2") (pinfunction "2_2") (pintype "passive"))
    )
    (net (code "48") (name "Net-(Q3-G)") (class "Default")
      (node (ref "Q3") (pin "1") (pinfunction "G_1") (pintype "bidirectional"))
      (node (ref "R34") (pin "2") (pinfunction "2_2") (pintype "passive"))
      (node (ref "R35") (pin "2") (pinfunction "2_2") (pintype "passive"))
    )
    (net (code "49") (name "Net-(Q4-G)") (class "Default")
      (node (ref "Q4") (pin "1") (pinfunction "G_1") (pintype "bidirectional"))
      (node (ref "R36") (pin "2") (pinfunction "2_2") (pintype "passive"))
      (node (ref "R37") (pin "2") (pinfunction "2_2") (pintype "passive"))
    )
    (net (code "50") (name "Net-(Q5-G)") (class "Default")
      (node (ref "Q5") (pin "1") (pinfunction "G_1") (pintype "bidirectional"))
      (node (ref "R38") (pin "2") (pinfunction "2_2") (pintype "passive"))
      (node (ref "R39") (pin "2") (pinfunction "2_2") (pintype "passive"))
    )
    (net (code "51") (name "Net-(Q6-G)") (class "Default")
      (node (ref "Q6") (pin "1") (pinfunction "G_1") (pintype "bidirectional"))
      (node (ref "R4") (pin "2") (pinfunction "2_2") (pintype "passive"))
      (node (ref "R5") (pin "2") (pinfunction "2_2") (pintype "passive"))
    )
    (net (code "52") (name "Net-(Q7-D)") (class "Default")
      (node (ref "Q7") (pin "3") (pinfunction "D_3") (pintype "passive"))
      (node (ref "Q8") (pin "3") (pinfunction "D_3") (pintype "passive"))
    )
    (net (code "53") (name "Net-(Q7-S)") (class "Default")
      (node (ref "C17") (pin "1") (pinfunction "1_1") (pintype "passive"))
      (node (ref "J2") (pin "2") (pinfunction "2_2") (pintype "bidirectional"))
      (node (ref "Q7") (pin "2") (pinfunction "S_2") (pintype "passive"))
      (node (ref "R2") (pin "2") (pinfunction "2_2") (pintype "passive"))
    )
    (net (code "54") (name "Net-(Q9-S)") (class "Default")
      (node (ref "C18") (pin "1") (pinfunction "1_1") (pintype "passive"))
      (node (ref "J2") (pin "3") (pinfunction "3_3") (pintype "bidirectional"))
      (node (ref "Q9") (pin "2") (pinfunction "S_2") (pintype "passive"))
      (node (ref "R30") (pin "2") (pinfunction "2_2") (pintype "passive"))
    )
    (net (code "55") (name "Net-(Q10-D)") (class "Default")
      (node (ref "Q10") (pin "3") (pinfunction "D_3") (pintype "passive"))
      (node (ref "Q9") (pin "3") (pinfunction "D_3") (pintype "passive"))
    )
    (net (code "56") (name "Net-(Q11-D)") (class "Default")
      (node (ref "Q11") (pin "3") (pinfunction "D_3") (pintype "passive"))
      (node (ref "Q12") (pin "3") (pinfunction "D_3") (pintype "passive"))
    )
    (net (code "57") (name "Net-(Q11-S)") (class "Default")
      (node (ref "C19") (pin "1") (pinfunction "1_1") (pintype "passive"))
      (node (ref "J2") (pin "6") (pinfunction "6_6") (pintype "bidirectional"))
      (node (ref "Q11") (pin "2") (pinfunction "S_2") (pintype "passive"))
      (node (ref "R41") (pin "2") (pinfunction "2_2") (pintype "passive"))
    )
    (net (code "58") (name "REL_CH_00") (class "Default")
      (node (ref "IC1") (pin "16") (pinfunction "IO13_16") (pintype "bidirectional"))
      (node (ref "IC5") (pin "2") (pinfunction "A_2") (pintype "bidirectional"))
    )
    (net (code "59") (name "REL_CH_01") (class "Default")
      (node (ref "IC1") (pin "13") (pinfunction "IO14_13") (pintype "bidirectional"))
      (node (ref "IC6") (pin "2") (pinfunction "A_2") (pintype "bidirectional"))
    )
    (net (code "60") (name "REL_CH_02") (class "Default")
      (node (ref "IC1") (pin "9") (pinfunction "IO33_9") (pintype "bidirectional"))
      (node (ref "IC7") (pin "2") (pinfunction "A_2") (pintype "bidirectional"))
    )
    (net (code "61") (name "REL_CH_03") (class "Default")
      (node (ref "IC1") (pin "8") (pinfunction "IO32_8") (pintype "bidirectional"))
      (node (ref "IC8") (pin "2") (pinfunction "A_2") (pintype "bidirectional"))
    )
    (net (code "62") (name "REL_CH_04") (class "Default")
      (node (ref "IC1") (pin "26") (pinfunction "IO4_26") (pintype "bidirectional"))
      (node (ref "IC9") (pin "2") (pinfunction "A_2") (pintype "bidirectional"))
    )
    (net (code "63") (name "REL_OUT_CH_00") (class "Default")
      (node (ref "J5") (pin "2") (pinfunction "2_2") (pintype "bidirectional"))
      (node (ref "Q2") (pin "2") (pinfunction "D_2") (pintype "bidirectional"))
    )
    (net (code "64") (name "REL_OUT_CH_01") (class "Default")
      (node (ref "J5") (pin "4") (pinfunction "4_4") (pintype "bidirectional"))
      (node (ref "Q3") (pin "2") (pinfunction "D_2") (pintype "bidirectional"))
    )
    (net (code "65") (name "REL_OUT_CH_02") (class "Default")
      (node (ref "J6") (pin "1") (pinfunction "1_1") (pintype "bidirectional"))
      (node (ref "Q4") (pin "2") (pinfunction "D_2") (pintype "bidirectional"))
    )
    (net (code "66") (name "REL_OUT_CH_03") (class "Default")
      (node (ref "J6") (pin "3") (pinfunction "3_3") (pintype "bidirectional"))
      (node (ref "Q5") (pin "2") (pinfunction "D_2") (pintype "bidirectional"))
    )
    (net (code "67") (name "REL_OUT_CH_04") (class "Default")
      (node (ref "J6") (pin "5") (pinfunction "5_5") (pintype "bidirectional"))
      (node (ref "Q6") (pin "2") (pinfunction "D_2") (pintype "bidirectional"))
    )
    (net (code "68") (name "RST") (class "Default")
      (node (ref "C10") (pin "1") (pinfunction "1_1") (pintype "passive"))
      (node (ref "IC1") (pin "3") (pinfunction "EN_3") (pintype "bidirectional"))
      (node (ref "PROG") (pin "5") (pinfunction "5_5") (pintype "passive"))
      (node (ref "R10") (pin "1") (pinfunction "1_1") (pintype "passive"))
    )
    (net (code "69") (name "RXD0") (class "Default")
      (node (ref "IC2") (pin "8") (pinfunction "RXD0/MODE0_8") (pintype "bidirectional"))
      (node (ref "R27") (pin "1") (pinfunction "1_1") (pintype "passive"))
      (node (ref "R9") (pin "2") (pinfunction "2_2") (pintype "passive"))
    )
    (net (code "70") (name "RXD1") (class "Default")
      (node (ref "IC2") (pin "7") (pinfunction "RXD1/MODE1_7") (pintype "bidirectional"))
      (node (ref "R26") (pin "1") (pinfunction "1_1") (pintype "passive"))
      (node (ref "R8") (pin "2") (pinfunction "2_2") (pintype "passive"))
    )
    (net (code "71") (name "VCCIO") (class "Default")
      (node (ref "J2") (pin "1") (pinfunction "1_1") (pintype "bidirectional"))
      (node (ref "J2") (pin "5") (pinfunction "5_5") (pintype "bidirectional"))
      (node (ref "Q11") (pin "1") (pinfunction "G_1") (pintype "passive"))
      (node (ref "Q7") (pin "1") (pinfunction "G_1") (pintype "passive"))
      (node (ref "Q9") (pin "1") (pinfunction "G_1") (pintype "passive"))
      (node (ref "R2") (pin "1") (pinfunction "1_1") (pintype "passive"))
      (node (ref "R30") (pin "1") (pinfunction "1_1") (pintype "passive"))
      (node (ref "R41") (pin "1") (pinfunction "1_1") (pintype "passive"))
      (node (ref "VIO") (pin "2") (pinfunction "2_2") (pintype "passive"))
      (node (ref "VIO") (pin "4") (pinfunction "4_4") (pintype "passive"))
      (node (ref "VIO") (pin "6") (pinfunction "6_6") (pintype "passive"))
    )
    (net (code "72") (name "unconnected-(IC1-CLK-Pad20)") (class "Default")
      (node (ref "IC1") (pin "20") (pinfunction "CLK_20") (pintype "bidirectional"))
    )
    (net (code "73") (name "unconnected-(IC1-CMD-Pad19)") (class "Default")
      (node (ref "IC1") (pin "19") (pinfunction "CMD_19") (pintype "bidirectional"))
    )
    (net (code "74") (name "unconnected-(IC1-IO2-Pad24)") (class "Default")
      (node (ref "IC1") (pin "24") (pinfunction "IO2_24") (pintype "bidirectional"))
    )
    (net (code "75") (name "unconnected-(IC1-IO5-Pad29)") (class "Default")
      (node (ref "IC1") (pin "29") (pinfunction "IO5_29") (pintype "bidirectional"))
    )
    (net (code "76") (name "unconnected-(IC1-IO12-Pad14)") (class "Default")
      (node (ref "IC1") (pin "14") (pinfunction "IO12_14") (pintype "bidirectional"))
    )
    (net (code "77") (name "unconnected-(IC1-IO15-Pad23)") (class "Default")
      (node (ref "IC1") (pin "23") (pinfunction "IO15_23") (pintype "bidirectional"))
    )
    (net (code "78") (name "unconnected-(IC1-IO16-Pad27)") (class "Default")
      (node (ref "IC1") (pin "27") (pinfunction "IO16_27") (pintype "bidirectional"))
    )
    (net (code "79") (name "unconnected-(IC1-NC-Pad32)") (class "Default")
      (node (ref "IC1") (pin "32") (pinfunction "NC_32") (pintype "no_connect"))
    )
    (net (code "80") (name "unconnected-(IC1-SD0-Pad21)") (class "Default")
      (node (ref "IC1") (pin "21") (pinfunction "SD0_21") (pintype "bidirectional"))
    )
    (net (code "81") (name "unconnected-(IC1-SD1-Pad22)") (class "Default")
      (node (ref "IC1") (pin "22") (pinfunction "SD1_22") (pintype "bidirectional"))
    )
    (net (code "82") (name "unconnected-(IC1-SD2-Pad17)") (class "Default")
      (node (ref "IC1") (pin "17") (pinfunction "SD2_17") (pintype "bidirectional"))
    )
    (net (code "83") (name "unconnected-(IC1-SD3-Pad18)") (class "Default")
      (node (ref "IC1") (pin "18") (pinfunction "SD3_18") (pintype "bidirectional"))
    )
    (net (code "84") (name "unconnected-(IC2-XTAL2-Pad4)") (class "Default")
      (node (ref "IC2") (pin "4") (pinfunction "XTAL2_4") (pintype "bidirectional"))
    )
    (net (code "85") (name "unconnected-(IC5-N.C.-Pad1)") (class "Default")
      (node (ref "IC5") (pin "1") (pinfunction "N.C._1") (pintype "no_connect"))
    )
    (net (code "86") (name "unconnected-(IC6-N.C.-Pad1)") (class "Default")
      (node (ref "IC6") (pin "1") (pinfunction "N.C._1") (pintype "no_connect"))
    )
    (net (code "87") (name "unconnected-(IC7-N.C.-Pad1)") (class "Default")
      (node (ref "IC7") (pin "1") (pinfunction "N.C._1") (pintype "no_connect"))
    )
    (net (code "88") (name "unconnected-(IC8-N.C.-Pad1)") (class "Default")
      (node (ref "IC8") (pin "1") (pinfunction "N.C._1") (pintype "no_connect"))
    )
    (net (code "89") (name "unconnected-(IC9-N.C.-Pad1)") (class "Default")
      (node (ref "IC9") (pin "1") (pinfunction "N.C._1") (pintype "no_connect"))
    )
    (net (code "90") (name "unconnected-(J3-NC-Pad7)") (class "Default")
      (node (ref "J3") (pin "7") (pinfunction "NC_7") (pintype "bidirectional"))
    )
  )
)
